# Adafruit_NeoPixel_Ring_24_B_-_Holder_2.net
KiCad netlist of a schematic drawn in EAGLE
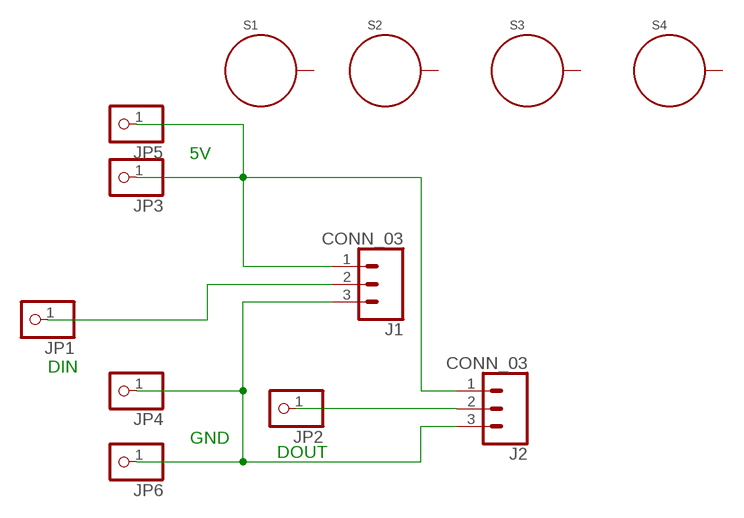
[diagram p0: schematic, sheet 1]

(export (version "E")
  (design (tool "Eeschema 10.0.6"))
  (components
    (comp (ref "J1")
      (value "CONN_03")
      (footprint "eagle-import:1X03_3.5MM_RA")
      (libsource (lib "eagle-import") (part "CONN_03"))
    )
    (comp (ref "J2")
      (value "CONN_03")
      (footprint "eagle-import:1X03_3.5MM_RA")
      (libsource (lib "eagle-import") (part "CONN_03"))
    )
    (comp (ref "JP1")
      (value "PINHD-1X1CB")
      (footprint "eagle-import:1X01-CLEANBIG")
      (libsource (lib "eagle-import") (part "PINHD-1X1CB"))
    )
    (comp (ref "JP2")
      (value "PINHD-1X1CB")
      (footprint "eagle-import:1X01-CLEANBIG")
      (libsource (lib "eagle-import") (part "PINHD-1X1CB"))
    )
    (comp (ref "JP3")
      (value "PINHD-1X1CB")
      (footprint "eagle-import:1X01-CLEANBIG")
      (libsource (lib "eagle-import") (part "PINHD-1X1CB"))
    )
    (comp (ref "JP4")
      (value "PINHD-1X1CB")
      (footprint "eagle-import:1X01-CLEANBIG")
      (libsource (lib "eagle-import") (part "PINHD-1X1CB"))
    )
    (comp (ref "JP5")
      (value "PINHD-1X1CB")
      (footprint "eagle-import:1X01-CLEANBIG")
      (libsource (lib "eagle-import") (part "PINHD-1X1CB"))
    )
    (comp (ref "JP6")
      (value "PINHD-1X1CB")
      (footprint "eagle-import:1X01-CLEANBIG")
      (libsource (lib "eagle-import") (part "PINHD-1X1CB"))
    )
    (comp (ref "S1")
      (value "STANDOFF_ELECTRICAL.17\"")
      (footprint "eagle-import:STANDOFF-ELECTRICAL")
      (libsource (lib "eagle-import") (part "STANDOFF_ELECTRICAL.17{dblquote}"))
    )
    (comp (ref "S2")
      (value "STANDOFF_ELECTRICAL.17\"")
      (footprint "eagle-import:STANDOFF-ELECTRICAL")
      (libsource (lib "eagle-import") (part "STANDOFF_ELECTRICAL.17{dblquote}"))
    )
    (comp (ref "S3")
      (value "STANDOFF_ELECTRICAL.17\"")
      (footprint "eagle-import:STANDOFF-ELECTRICAL")
      (libsource (lib "eagle-import") (part "STANDOFF_ELECTRICAL.17{dblquote}"))
    )
    (comp (ref "S4")
      (value "STANDOFF_ELECTRICAL.17\"")
      (footprint "eagle-import:STANDOFF-ELECTRICAL")
      (libsource (lib "eagle-import") (part "STANDOFF_ELECTRICAL.17{dblquote}"))
    )
  )
  (nets
    (net (code "1") (name "Net-(J1-Pad1)") (class "Default")
      (node (ref "J1") (pin "1") (pinfunction "1_1") (pintype "passive"))
      (node (ref "J2") (pin "1") (pinfunction "1_1") (pintype "passive"))
      (node (ref "JP3") (pin "1") (pinfunction "1_1") (pintype "passive"))
      (node (ref "JP5") (pin "1") (pinfunction "1_1") (pintype "passive"))
    )
    (net (code "2") (name "Net-(J1-Pad2)") (class "Default")
      (node (ref "J1") (pin "2") (pinfunction "2_2") (pintype "passive"))
      (node (ref "JP1") (pin "1") (pinfunction "1_1") (pintype "passive"))
    )
    (net (code "3") (name "Net-(J1-Pad3)") (class "Default")
      (node (ref "J1") (pin "3") (pinfunction "3_3") (pintype "passive"))
      (node (ref "J2") (pin "3") (pinfunction "3_3") (pintype "passive"))
      (node (ref "JP4") (pin "1") (pinfunction "1_1") (pintype "passive"))
      (node (ref "JP6") (pin "1") (pinfunction "1_1") (pintype "passive"))
    )
    (net (code "4") (name "Net-(J2-Pad2)") (class "Default")
      (node (ref "J2") (pin "2") (pinfunction "2_2") (pintype "passive"))
      (node (ref "JP2") (pin "1") (pinfunction "1_1") (pintype "passive"))
    )
    (net (code "5") (name "unconnected-(S1-P$1-PadP1)") (class "Default")
      (node (ref "S1") (pin "P1") (pinfunction "P$1_P1") (pintype "bidirectional"))
    )
    (net (code "6") (name "unconnected-(S2-P$1-PadP1)") (class "Default")
      (node (ref "S2") (pin "P1") (pinfunction "P$1_P1") (pintype "bidirectional"))
    )
    (net (code "7") (name "unconnected-(S3-P$1-PadP1)") (class "Default")
      (node (ref "S3") (pin "P1") (pinfunction "P$1_P1") (pintype "bidirectional"))
    )
    (net (code "8") (name "unconnected-(S4-P$1-PadP1)") (class "Default")
      (node (ref "S4") (pin "P1") (pinfunction "P$1_P1") (pintype "bidirectional"))
    )
  )
)
